# 2-22.net
KiCad netlist of a schematic drawn in Altium Designer
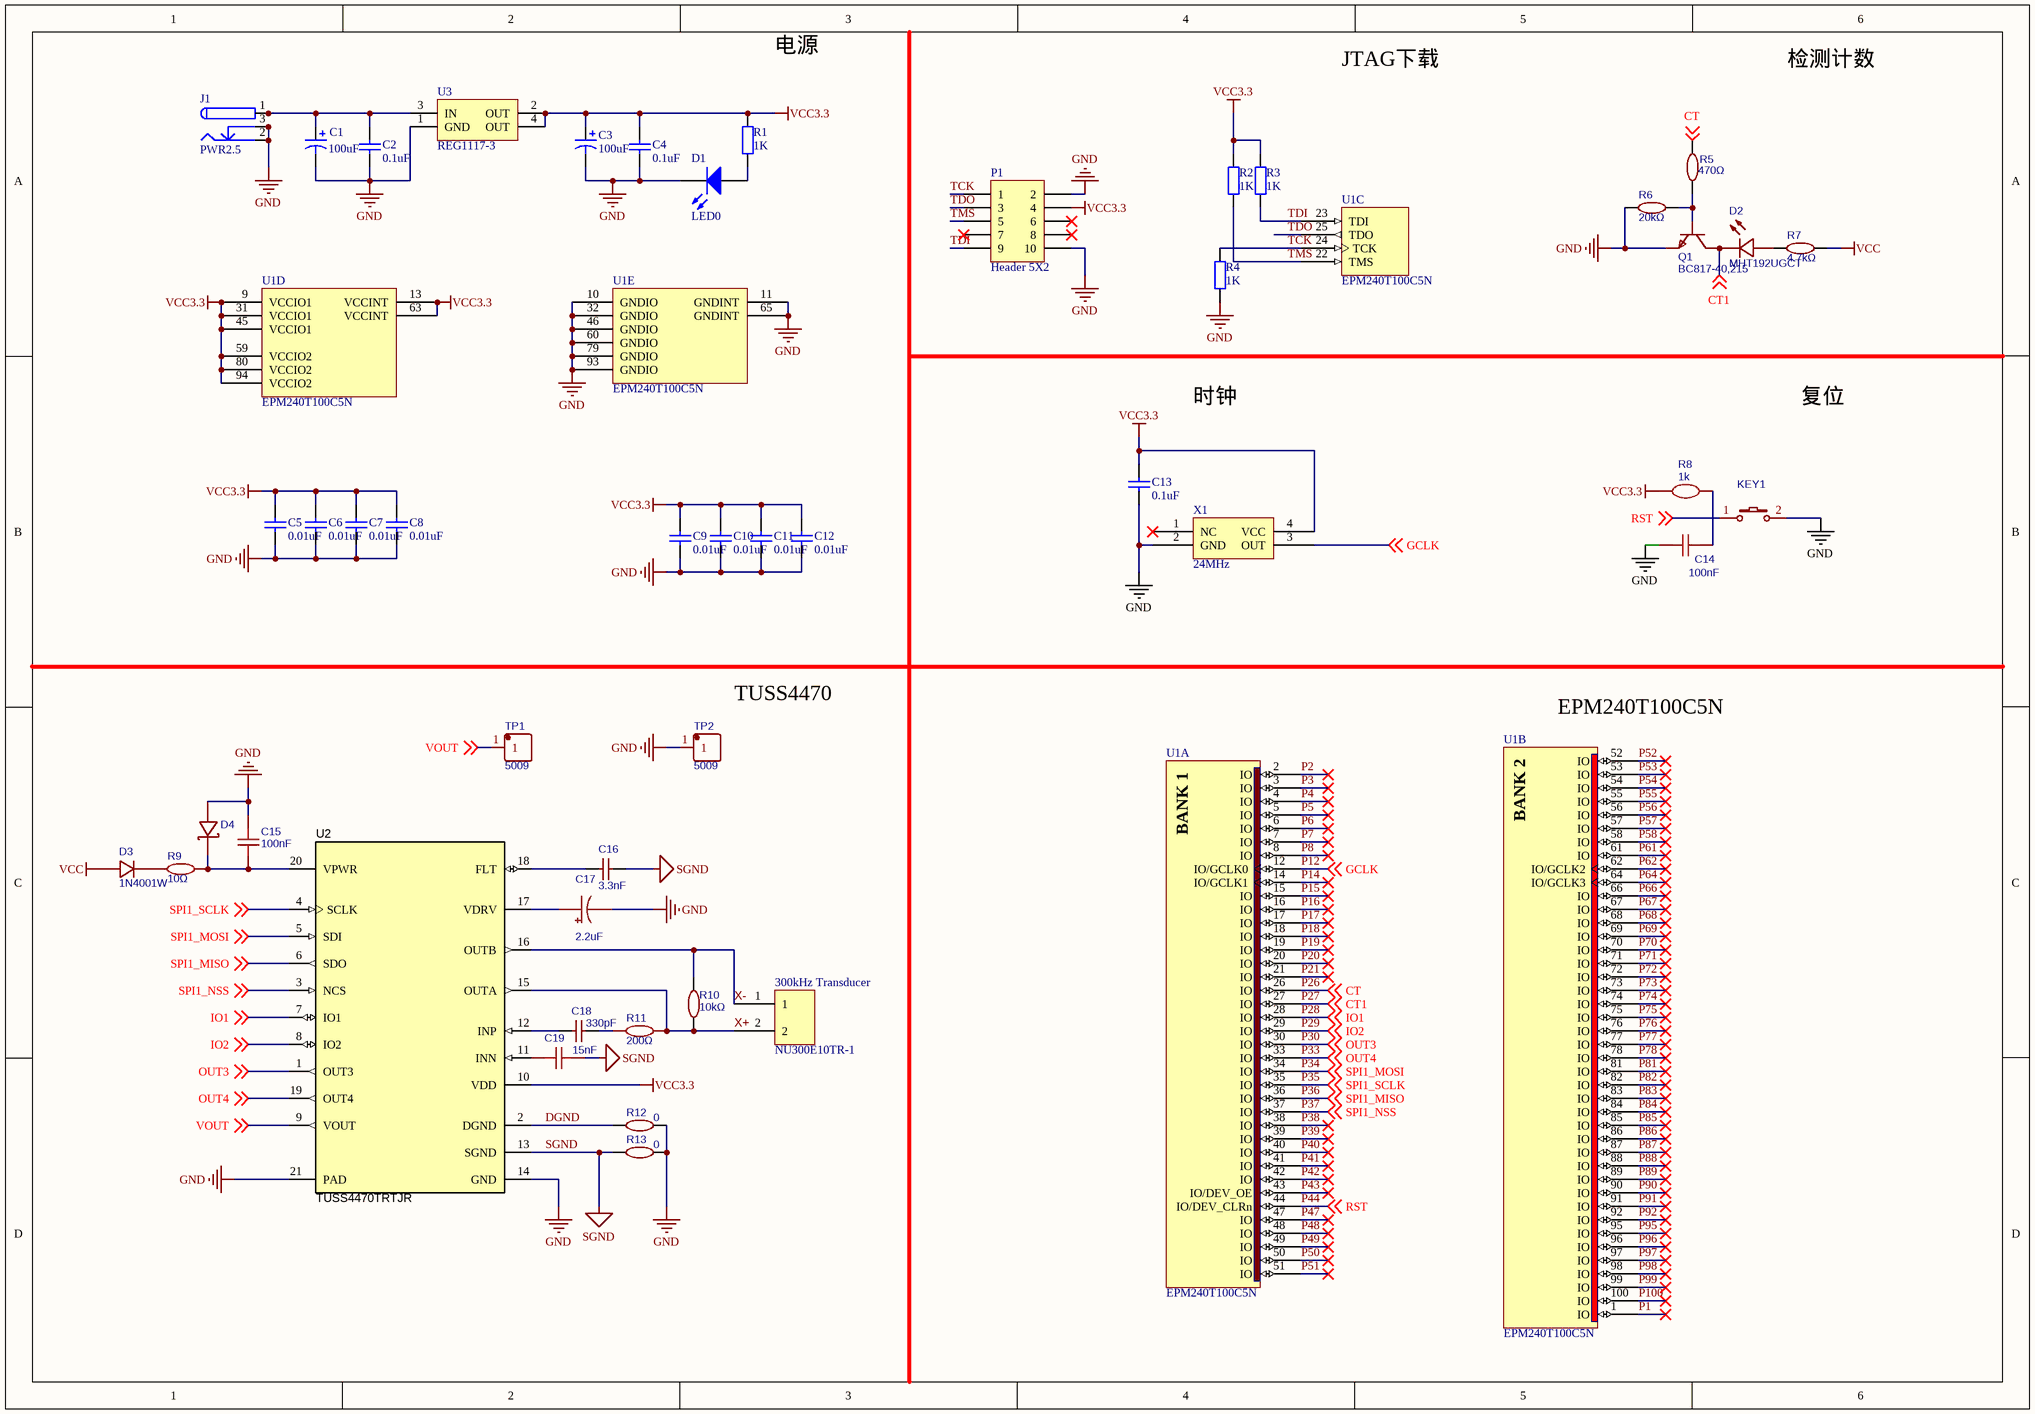
[diagram p0: 超声波接近电路2-22.SchDoc]

(export (version "E")
  (design (tool "Eeschema 10.0.6"))
  (components
    (comp (ref "300kHz Transducer")
      (value "NU300E10TR-1")
      (footprint "NU300E10TR-1")
      (libsource (lib "超声波接近电路") (part "NU300E10TR-1"))
    )
    (comp (ref "C1")
      (value "100uF")
      (footprint "CAP-SMD_L3.2-W1.6-RD")
      (description "Polarized Capacitor (Radial)")
      (fields (field (name "Comment") "Cap Pol1") (field (name "PUBLISHER") "Altium Limited"))
      (libsource (lib "Miscellaneous Devices") (part "Cap Pol1"))
    )
    (comp (ref "C2")
      (value "0.1uF")
      (footprint "C0603")
      (description "Capacitor")
      (fields (field (name "Comment") "Cap") (field (name "PUBLISHER") "Altium Limited"))
      (libsource (lib "Miscellaneous Devices") (part "Cap"))
    )
    (comp (ref "C3")
      (value "100uF")
      (footprint "CAP-SMD_L3.2-W1.6-RD")
      (description "Polarized Capacitor (Radial)")
      (fields (field (name "Comment") "Cap Pol1") (field (name "PUBLISHER") "Altium Limited"))
      (libsource (lib "Miscellaneous Devices") (part "Cap Pol1"))
    )
    (comp (ref "C4")
      (value "0.1uF")
      (footprint "C0603")
      (description "Capacitor")
      (fields (field (name "Comment") "Cap") (field (name "PUBLISHER") "Altium Limited"))
      (libsource (lib "Miscellaneous Devices") (part "Cap"))
    )
    (comp (ref "C5")
      (value "0.01uF")
      (footprint "C0603")
      (description "Capacitor")
      (fields (field (name "Comment") "Cap") (field (name "PUBLISHER") "Altium Limited"))
      (libsource (lib "Miscellaneous Devices") (part "Cap"))
    )
    (comp (ref "C6")
      (value "0.01uF")
      (footprint "C0603")
      (description "Capacitor")
      (fields (field (name "Comment") "Cap") (field (name "PUBLISHER") "Altium Limited"))
      (libsource (lib "Miscellaneous Devices") (part "Cap"))
    )
    (comp (ref "C7")
      (value "0.01uF")
      (footprint "C0603")
      (description "Capacitor")
      (fields (field (name "Comment") "Cap") (field (name "PUBLISHER") "Altium Limited"))
      (libsource (lib "Miscellaneous Devices") (part "Cap"))
    )
    (comp (ref "C8")
      (value "0.01uF")
      (footprint "C0603")
      (description "Capacitor")
      (fields (field (name "Comment") "Cap") (field (name "PUBLISHER") "Altium Limited"))
      (libsource (lib "Miscellaneous Devices") (part "Cap"))
    )
    (comp (ref "C9")
      (value "0.01uF")
      (footprint "C0603")
      (description "Capacitor")
      (fields (field (name "Comment") "Cap") (field (name "PUBLISHER") "Altium Limited"))
      (libsource (lib "Miscellaneous Devices") (part "Cap"))
    )
    (comp (ref "C10")
      (value "0.01uF")
      (footprint "C0603")
      (description "Capacitor")
      (fields (field (name "Comment") "Cap") (field (name "PUBLISHER") "Altium Limited"))
      (libsource (lib "Miscellaneous Devices") (part "Cap"))
    )
    (comp (ref "C11")
      (value "0.01uF")
      (footprint "C0603")
      (description "Capacitor")
      (fields (field (name "Comment") "Cap") (field (name "PUBLISHER") "Altium Limited"))
      (libsource (lib "Miscellaneous Devices") (part "Cap"))
    )
    (comp (ref "C12")
      (value "0.01uF")
      (footprint "C0603")
      (description "Capacitor")
      (fields (field (name "Comment") "Cap") (field (name "PUBLISHER") "Altium Limited"))
      (libsource (lib "Miscellaneous Devices") (part "Cap"))
    )
    (comp (ref "C13")
      (value "0.1uF")
      (footprint "C0603")
      (description "Capacitor")
      (fields (field (name "Comment") "Cap") (field (name "PUBLISHER") "Altium Limited"))
      (libsource (lib "Miscellaneous Devices") (part "Cap"))
    )
    (comp (ref "C14")
      (value "100nF")
      (footprint "C0603")
      (fields (field (name "CONTRIBUTOR") "LCEDA_Lib"))
      (libsource (lib "altium-import") (part "root_2_100nF_"))
    )
    (comp (ref "C15")
      (value "100nF")
      (footprint "C0603")
      (fields
        (field (name "BOM_MANUFACTURER PART") "CC0603KRX7R9BB104")
        (field (name "BOM_SUPPLIER PART") "C14663")
      )
      (libsource (lib "超声波接近电路") (part "100nF"))
    )
    (comp (ref "C16")
      (value "3.3nF")
      (footprint "C0603")
      (fields
        (field (name "BOM_MANUFACTURER PART") "GRM1885C1H332JA01D")
        (field (name "BOM_SUPPLIER PART") "C77036")
      )
      (libsource (lib "超声波接近电路") (part "3.3nF"))
    )
    (comp (ref "C17")
      (value "2.2uF")
      (footprint "CAP-SMD_L3.2-W1.6-RD")
      (fields
        (field (name "BOM_SUPPLIER PART") "C122264")
        (field (name "BOM_MANUFACTURER PART") "T491A225K035AT")
        (field (name "CONTRIBUTOR") "LCSC")
      )
      (libsource (lib "超声波接近电路") (part "2.2uF_1"))
    )
    (comp (ref "C18")
      (value "330pF")
      (footprint "C0603")
      (fields
        (field (name "BOM_MANUFACTURER PART") "CL10C331JB8NNNC")
        (field (name "BOM_SUPPLIER PART") "C1664")
      )
      (libsource (lib "超声波接近电路") (part "330pF"))
    )
    (comp (ref "C19")
      (value "15nF")
      (footprint "C0603")
      (fields
        (field (name "BOM_SUPPLIER PART") "C519550")
        (field (name "BOM_MANUFACTURER PART") "CC0603JRX7R9BB153")
        (field (name "CONTRIBUTOR") "LCSC")
      )
      (libsource (lib "超声波接近电路") (part "15nF"))
    )
    (comp (ref "D1")
      (value "LED0")
      (footprint "LED0603-RD_RED")
      (description "Typical INFRARED GaAs LED")
      (fields (field (name "PUBLISHER") "Altium Limited"))
      (libsource (lib "Miscellaneous Devices") (part "LED0"))
    )
    (comp (ref "D2")
      (value "MHT192UGCT")
      (footprint "LED0603-RD_GREEN")
      (fields (field (name "BOM_SUPPLIER PART") "C389519") (field (name "CONTRIBUTOR") "LCSC"))
      (libsource (lib "超声波接近电路") (part "MHT192UGCT"))
    )
    (comp (ref "D3")
      (value "1N4001W")
      (footprint "SOD-123F_L2.8-W1.8-LS3.7-RD")
      (fields (field (name "BOM_SUPPLIER PART") "C162732") (field (name "CONTRIBUTOR") "LCSC"))
      (libsource (lib "超声波接近电路") (part "1N4001W"))
    )
    (comp (ref "D4")
      (value "SMF36A_C353286")
      (footprint "SOD-123FL_L2.7-W1.8-LS3.8-RD")
      (fields
        (field (name "BOM_SUPPLIER PART") "C353286")
        (field (name "BOM_MANUFACTURER PART") "SMF36A")
        (field (name "CONTRIBUTOR") "LCSC")
      )
      (libsource (lib "超声波接近电路") (part "SMF36A_C353286"))
    )
    (comp (ref "J1")
      (value "PWR2.5")
      (footprint "KLD-0202")
      (description "Low Voltage Power Supply Connector")
      (fields (field (name "PUBLISHER") "Altium Limited"))
      (libsource (lib "Miscellaneous Connectors") (part "PWR2.5"))
    )
    (comp (ref "KEY1")
      (value "K2-3.6×6.1_SMD")
      (footprint "KEY-SMD_2P-L6.2-W3.6-LS8.0")
      (fields
        (field (name "BOM_SUPPLIER PART") "C118141")
        (field (name "BOM_MANUFACTURER PART") "K2-1107ST-A4SW-06")
        (field (name "CONTRIBUTOR") "LCEDA_Lib")
      )
      (libsource (lib "altium-import") (part "root_0_K2-3.6×6.1_SMD_"))
    )
    (comp (ref "P1")
      (value "Header 5X2")
      (footprint "HDR2X5")
      (description "Header, 5-Pin, Dual row")
      (fields (field (name "PUBLISHER") "Altium Limited"))
      (libsource (lib "Miscellaneous Connectors") (part "Header 5X2"))
    )
    (comp (ref "Q1")
      (value "BC817-40,215")
      (footprint "SOT-23-3_L2.9-W1.6-P1.90-LS2.8-BR")
      (fields (field (name "BOM_SUPPLIER PART") "C52801"))
      (libsource (lib "超声波接近电路") (part "BC817-40,215"))
    )
    (comp (ref "R1")
      (value "1K")
      (footprint "R0603")
      (description "Resistor")
      (fields (field (name "Comment") "Res2") (field (name "PUBLISHER") "Altium Limited"))
      (libsource (lib "Miscellaneous Devices") (part "Res2"))
    )
    (comp (ref "R2")
      (value "1K")
      (footprint "R0603")
      (description "Resistor")
      (fields (field (name "Comment") "Res2") (field (name "PUBLISHER") "Altium Limited"))
      (libsource (lib "Miscellaneous Devices") (part "Res2"))
    )
    (comp (ref "R3")
      (value "1K")
      (footprint "R0603")
      (description "Resistor")
      (fields (field (name "Comment") "Res2") (field (name "PUBLISHER") "Altium Limited"))
      (libsource (lib "Miscellaneous Devices") (part "Res2"))
    )
    (comp (ref "R4")
      (value "1K")
      (footprint "R0603")
      (description "Resistor")
      (fields (field (name "Comment") "Res2") (field (name "PUBLISHER") "Altium Limited"))
      (libsource (lib "Miscellaneous Devices") (part "Res2"))
    )
    (comp (ref "R5")
      (value "470Ω")
      (footprint "R0603")
      (fields
        (field (name "BOM_MANUFACTURER PART") "0603WAJ0471T5E")
        (field (name "BOM_SUPPLIER PART") "C25241")
      )
      (libsource (lib "超声波接近电路") (part "470Ω"))
    )
    (comp (ref "R6")
      (value "20kΩ")
      (footprint "R0603")
      (fields
        (field (name "BOM_MANUFACTURER PART") "0603WAF2002T5E")
        (field (name "BOM_SUPPLIER PART") "C4184")
      )
      (libsource (lib "超声波接近电路") (part "20kΩ"))
    )
    (comp (ref "R7")
      (value "4.7kΩ")
      (footprint "R0603")
      (fields
        (field (name "BOM_MANUFACTURER PART") "0603WAF4701T5E")
        (field (name "BOM_SUPPLIER PART") "C23162")
      )
      (libsource (lib "超声波接近电路") (part "4.7kΩ"))
    )
    (comp (ref "R8")
      (value "1k")
      (footprint "R0603")
      (fields (field (name "CONTRIBUTOR") "LCEDA_Lib"))
      (libsource (lib "altium-import") (part "root_2_1k_"))
    )
    (comp (ref "R9")
      (value "10Ω")
      (footprint "R0603")
      (fields
        (field (name "BOM_SUPPLIER PART") "C441879")
        (field (name "BOM_MANUFACTURER PART") "ERJPA3J100V")
        (field (name "CONTRIBUTOR") "LCSC")
      )
      (libsource (lib "超声波接近电路") (part "10Ω"))
    )
    (comp (ref "R10")
      (value "10kΩ")
      (footprint "R0603")
      (fields
        (field (name "BOM_MANUFACTURER PART") "0603WAF1002T5E")
        (field (name "BOM_SUPPLIER PART") "C25804")
      )
      (libsource (lib "超声波接近电路") (part "10kΩ"))
    )
    (comp (ref "R11")
      (value "200Ω")
      (footprint "R0603")
      (fields
        (field (name "BOM_SUPPLIER PART") "C254528")
        (field (name "BOM_MANUFACTURER PART") "ERJ-PA3F2000V")
        (field (name "CONTRIBUTOR") "LCSC")
      )
      (libsource (lib "超声波接近电路") (part "200Ω"))
    )
    (comp (ref "R12")
      (value "0")
      (footprint "R0603")
      (fields
        (field (name "BOM_MANUFACTURER PART") "RC0603JR-070RL")
        (field (name "BOM_SUPPLIER PART") "C95177")
      )
      (libsource (lib "超声波接近电路") (part "0_1"))
    )
    (comp (ref "R13")
      (value "0")
      (footprint "R0603")
      (fields
        (field (name "BOM_MANUFACTURER PART") "RC0603JR-070RL")
        (field (name "BOM_SUPPLIER PART") "C95177")
      )
      (libsource (lib "超声波接近电路") (part "0_1"))
    )
    (comp (ref "TP1")
      (value "5009")
      (footprint "TEST-TH_BD3.18-P1.93")
      (fields (field (name "BOM_SUPPLIER PART") "C238126") (field (name "CONTRIBUTOR") "LCSC"))
      (libsource (lib "超声波接近电路") (part "5009"))
    )
    (comp (ref "TP2")
      (value "5009")
      (footprint "TEST-TH_BD3.18-P1.93")
      (fields (field (name "BOM_SUPPLIER PART") "C238126") (field (name "CONTRIBUTOR") "LCSC"))
      (libsource (lib "超声波接近电路") (part "5009"))
    )
    (comp (ref "U1")
      (value "EPM240T100C5N")
      (footprint "TQFP-100_L14.0-W14.0-P0.50-LS16.0-BL")
      (fields (field (name "PUBLISHER") "Altium Limited"))
      (libsource (lib "CPLD实验板") (part "EPM240T100C5N"))
    )
    (comp (ref "U2")
      (value "TUSS4470TRTJR")
      (footprint "QFN-20_L4.0-W4.0-P0.50-TL-EP2.7")
      (description "Ultrasonic Sensor Signal Conditioner IC for Directly")
      (fields
        (field (name "MANUFACTURER") "Texas Instruments")
        (field (name "ALTERNATE PARTNUMBER") "PGA44801RTJT")
        (field (name "PARTNUMBER") "TUSS4470TRTJR")
      )
      (libsource (lib "超声波接近电路") (part "CMP-0081414-4"))
    )
    (comp (ref "U3")
      (value "REG1117-3")
      (footprint "ZZ311")
      (description "800mA Low Dropout Positive Regulator Fixed 2.85V,3V,3.3V and 5V")
      (fields (field (name "PUBLISHER") "Altium Limited"))
      (libsource (lib "BB Power Mgt Voltage Regulator") (part "REG1117-3"))
    )
    (comp (ref "X1")
      (value "24MHz")
      (footprint "OSC-SMD_4P-L7.0-W5.0-BL_SIT1602")
      (libsource (lib "Schlib1") (part "oscillator"))
    )
  )
  (nets
    (net (code "1") (name "/DGND") (class "Default")
      (node (ref "R12") (pin "1") (pinfunction "1_1") (pintype "passive"))
      (node (ref "U2") (pin "2") (pinfunction "DGND_2") (pintype "power_in"))
    )
    (net (code "2") (name "/P1") (class "Default")
      (node (ref "U1") (pin "1") (pinfunction "IO_1") (pintype "bidirectional+no_connect"))
    )
    (net (code "3") (name "/P2") (class "Default")
      (node (ref "U1") (pin "2") (pinfunction "IO_2") (pintype "bidirectional+no_connect"))
    )
    (net (code "4") (name "/P3") (class "Default")
      (node (ref "U1") (pin "3") (pinfunction "IO_3") (pintype "bidirectional+no_connect"))
    )
    (net (code "5") (name "/P4") (class "Default")
      (node (ref "U1") (pin "4") (pinfunction "IO_4") (pintype "bidirectional+no_connect"))
    )
    (net (code "6") (name "/P5") (class "Default")
      (node (ref "U1") (pin "5") (pinfunction "IO_5") (pintype "bidirectional+no_connect"))
    )
    (net (code "7") (name "/P6") (class "Default")
      (node (ref "U1") (pin "6") (pinfunction "IO_6") (pintype "bidirectional+no_connect"))
    )
    (net (code "8") (name "/P7") (class "Default")
      (node (ref "U1") (pin "7") (pinfunction "IO_7") (pintype "bidirectional+no_connect"))
    )
    (net (code "9") (name "/P8") (class "Default")
      (node (ref "U1") (pin "8") (pinfunction "IO_8") (pintype "bidirectional+no_connect"))
    )
    (net (code "10") (name "/P14") (class "Default")
      (node (ref "U1") (pin "14") (pinfunction "IO/GCLK1_14") (pintype "bidirectional+no_connect"))
    )
    (net (code "11") (name "/P15") (class "Default")
      (node (ref "U1") (pin "15") (pinfunction "IO_15") (pintype "bidirectional+no_connect"))
    )
    (net (code "12") (name "/P16") (class "Default")
      (node (ref "U1") (pin "16") (pinfunction "IO_16") (pintype "bidirectional+no_connect"))
    )
    (net (code "13") (name "/P17") (class "Default")
      (node (ref "U1") (pin "17") (pinfunction "IO_17") (pintype "bidirectional+no_connect"))
    )
    (net (code "14") (name "/P18") (class "Default")
      (node (ref "U1") (pin "18") (pinfunction "IO_18") (pintype "bidirectional+no_connect"))
    )
    (net (code "15") (name "/P19") (class "Default")
      (node (ref "U1") (pin "19") (pinfunction "IO_19") (pintype "bidirectional+no_connect"))
    )
    (net (code "16") (name "/P20") (class "Default")
      (node (ref "U1") (pin "20") (pinfunction "IO_20") (pintype "bidirectional+no_connect"))
    )
    (net (code "17") (name "/P21") (class "Default")
      (node (ref "U1") (pin "21") (pinfunction "IO_21") (pintype "bidirectional+no_connect"))
    )
    (net (code "18") (name "/P38") (class "Default")
      (node (ref "U1") (pin "38") (pinfunction "IO_38") (pintype "bidirectional+no_connect"))
    )
    (net (code "19") (name "/P39") (class "Default")
      (node (ref "U1") (pin "39") (pinfunction "IO_39") (pintype "bidirectional+no_connect"))
    )
    (net (code "20") (name "/P40") (class "Default")
      (node (ref "U1") (pin "40") (pinfunction "IO_40") (pintype "bidirectional+no_connect"))
    )
    (net (code "21") (name "/P41") (class "Default")
      (node (ref "U1") (pin "41") (pinfunction "IO_41") (pintype "bidirectional+no_connect"))
    )
    (net (code "22") (name "/P42") (class "Default")
      (node (ref "U1") (pin "42") (pinfunction "IO_42") (pintype "bidirectional+no_connect"))
    )
    (net (code "23") (name "/P43") (class "Default")
      (node (ref "U1") (pin "43") (pinfunction "IO/DEV_OE_43") (pintype "bidirectional+no_connect"))
    )
    (net (code "24") (name "/P47") (class "Default")
      (node (ref "U1") (pin "47") (pinfunction "IO_47") (pintype "bidirectional+no_connect"))
    )
    (net (code "25") (name "/P48") (class "Default")
      (node (ref "U1") (pin "48") (pinfunction "IO_48") (pintype "bidirectional+no_connect"))
    )
    (net (code "26") (name "/P49") (class "Default")
      (node (ref "U1") (pin "49") (pinfunction "IO_49") (pintype "bidirectional+no_connect"))
    )
    (net (code "27") (name "/P50") (class "Default")
      (node (ref "U1") (pin "50") (pinfunction "IO_50") (pintype "bidirectional+no_connect"))
    )
    (net (code "28") (name "/P51") (class "Default")
      (node (ref "U1") (pin "51") (pinfunction "IO_51") (pintype "bidirectional+no_connect"))
    )
    (net (code "29") (name "/P52") (class "Default")
      (node (ref "U1") (pin "52") (pinfunction "IO_52") (pintype "bidirectional+no_connect"))
    )
    (net (code "30") (name "/P53") (class "Default")
      (node (ref "U1") (pin "53") (pinfunction "IO_53") (pintype "bidirectional+no_connect"))
    )
    (net (code "31") (name "/P54") (class "Default")
      (node (ref "U1") (pin "54") (pinfunction "IO_54") (pintype "bidirectional+no_connect"))
    )
    (net (code "32") (name "/P55") (class "Default")
      (node (ref "U1") (pin "55") (pinfunction "IO_55") (pintype "bidirectional+no_connect"))
    )
    (net (code "33") (name "/P56") (class "Default")
      (node (ref "U1") (pin "56") (pinfunction "IO_56") (pintype "bidirectional+no_connect"))
    )
    (net (code "34") (name "/P57") (class "Default")
      (node (ref "U1") (pin "57") (pinfunction "IO_57") (pintype "bidirectional+no_connect"))
    )
    (net (code "35") (name "/P58") (class "Default")
      (node (ref "U1") (pin "58") (pinfunction "IO_58") (pintype "bidirectional+no_connect"))
    )
    (net (code "36") (name "/P61") (class "Default")
      (node (ref "U1") (pin "61") (pinfunction "IO_61") (pintype "bidirectional+no_connect"))
    )
    (net (code "37") (name "/P62") (class "Default")
      (node (ref "U1") (pin "62") (pinfunction "IO/GCLK2_62") (pintype "bidirectional+no_connect"))
    )
    (net (code "38") (name "/P64") (class "Default")
      (node (ref "U1") (pin "64") (pinfunction "IO/GCLK3_64") (pintype "bidirectional+no_connect"))
    )
    (net (code "39") (name "/P66") (class "Default")
      (node (ref "U1") (pin "66") (pinfunction "IO_66") (pintype "bidirectional+no_connect"))
    )
    (net (code "40") (name "/P67") (class "Default")
      (node (ref "U1") (pin "67") (pinfunction "IO_67") (pintype "bidirectional+no_connect"))
    )
    (net (code "41") (name "/P68") (class "Default")
      (node (ref "U1") (pin "68") (pinfunction "IO_68") (pintype "bidirectional+no_connect"))
    )
    (net (code "42") (name "/P69") (class "Default")
      (node (ref "U1") (pin "69") (pinfunction "IO_69") (pintype "bidirectional+no_connect"))
    )
    (net (code "43") (name "/P70") (class "Default")
      (node (ref "U1") (pin "70") (pinfunction "IO_70") (pintype "bidirectional+no_connect"))
    )
    (net (code "44") (name "/P71") (class "Default")
      (node (ref "U1") (pin "71") (pinfunction "IO_71") (pintype "bidirectional+no_connect"))
    )
    (net (code "45") (name "/P72") (class "Default")
      (node (ref "U1") (pin "72") (pinfunction "IO_72") (pintype "bidirectional+no_connect"))
    )
    (net (code "46") (name "/P73") (class "Default")
      (node (ref "U1") (pin "73") (pinfunction "IO_73") (pintype "bidirectional+no_connect"))
    )
    (net (code "47") (name "/P74") (class "Default")
      (node (ref "U1") (pin "74") (pinfunction "IO_74") (pintype "bidirectional+no_connect"))
    )
    (net (code "48") (name "/P75") (class "Default")
      (node (ref "U1") (pin "75") (pinfunction "IO_75") (pintype "bidirectional+no_connect"))
    )
    (net (code "49") (name "/P76") (class "Default")
      (node (ref "U1") (pin "76") (pinfunction "IO_76") (pintype "bidirectional+no_connect"))
    )
    (net (code "50") (name "/P77") (class "Default")
      (node (ref "U1") (pin "77") (pinfunction "IO_77") (pintype "bidirectional+no_connect"))
    )
    (net (code "51") (name "/P78") (class "Default")
      (node (ref "U1") (pin "78") (pinfunction "IO_78") (pintype "bidirectional+no_connect"))
    )
    (net (code "52") (name "/P81") (class "Default")
      (node (ref "U1") (pin "81") (pinfunction "IO_81") (pintype "bidirectional+no_connect"))
    )
    (net (code "53") (name "/P82") (class "Default")
      (node (ref "U1") (pin "82") (pinfunction "IO_82") (pintype "bidirectional+no_connect"))
    )
    (net (code "54") (name "/P83") (class "Default")
      (node (ref "U1") (pin "83") (pinfunction "IO_83") (pintype "bidirectional+no_connect"))
    )
    (net (code "55") (name "/P84") (class "Default")
      (node (ref "U1") (pin "84") (pinfunction "IO_84") (pintype "bidirectional+no_connect"))
    )
    (net (code "56") (name "/P85") (class "Default")
      (node (ref "U1") (pin "85") (pinfunction "IO_85") (pintype "bidirectional+no_connect"))
    )
    (net (code "57") (name "/P86") (class "Default")
      (node (ref "U1") (pin "86") (pinfunction "IO_86") (pintype "bidirectional+no_connect"))
    )
    (net (code "58") (name "/P87") (class "Default")
      (node (ref "U1") (pin "87") (pinfunction "IO_87") (pintype "bidirectional+no_connect"))
    )
    (net (code "59") (name "/P88") (class "Default")
      (node (ref "U1") (pin "88") (pinfunction "IO_88") (pintype "bidirectional+no_connect"))
    )
    (net (code "60") (name "/P89") (class "Default")
      (node (ref "U1") (pin "89") (pinfunction "IO_89") (pintype "bidirectional+no_connect"))
    )
    (net (code "61") (name "/P90") (class "Default")
      (node (ref "U1") (pin "90") (pinfunction "IO_90") (pintype "bidirectional+no_connect"))
    )
    (net (code "62") (name "/P91") (class "Default")
      (node (ref "U1") (pin "91") (pinfunction "IO_91") (pintype "bidirectional+no_connect"))
    )
    (net (code "63") (name "/P92") (class "Default")
      (node (ref "U1") (pin "92") (pinfunction "IO_92") (pintype "bidirectional+no_connect"))
    )
    (net (code "64") (name "/P95") (class "Default")
      (node (ref "U1") (pin "95") (pinfunction "IO_95") (pintype "bidirectional+no_connect"))
    )
    (net (code "65") (name "/P96") (class "Default")
      (node (ref "U1") (pin "96") (pinfunction "IO_96") (pintype "bidirectional+no_connect"))
    )
    (net (code "66") (name "/P97") (class "Default")
      (node (ref "U1") (pin "97") (pinfunction "IO_97") (pintype "bidirectional+no_connect"))
    )
    (net (code "67") (name "/P98") (class "Default")
      (node (ref "U1") (pin "98") (pinfunction "IO_98") (pintype "bidirectional+no_connect"))
    )
    (net (code "68") (name "/P99") (class "Default")
      (node (ref "U1") (pin "99") (pinfunction "IO_99") (pintype "bidirectional+no_connect"))
    )
    (net (code "69") (name "/P100") (class "Default")
      (node (ref "U1") (pin "100") (pinfunction "IO_100") (pintype "bidirectional+no_connect"))
    )
    (net (code "70") (name "/TCK") (class "Default")
      (node (ref "P1") (pin "1") (pinfunction "1_1") (pintype "passive"))
      (node (ref "R4") (pin "2") (pinfunction "2_2") (pintype "passive"))
      (node (ref "U1") (pin "24") (pinfunction "TCK_24") (pintype "input"))
    )
    (net (code "71") (name "/TDI") (class "Default")
      (node (ref "P1") (pin "9") (pinfunction "9_9") (pintype "passive"))
      (node (ref "R3") (pin "1") (pinfunction "1_1") (pintype "passive"))
      (node (ref "U1") (pin "23") (pinfunction "TDI_23") (pintype "input"))
    )
    (net (code "72") (name "/TDO") (class "Default")
      (node (ref "P1") (pin "3") (pinfunction "3_3") (pintype "passive"))
      (node (ref "U1") (pin "25") (pinfunction "TDO_25") (pintype "output"))
    )
    (net (code "73") (name "/TMS") (class "Default")
      (node (ref "P1") (pin "5") (pinfunction "5_5") (pintype "passive"))
      (node (ref "R2") (pin "1") (pinfunction "1_1") (pintype "passive"))
      (node (ref "U1") (pin "22") (pinfunction "TMS_22") (pintype "input"))
    )
    (net (code "74") (name "/X+") (class "Default")
      (node (ref "300kHz Transducer") (pin "2") (pinfunction "2_2") (pintype "passive"))
      (node (ref "R10") (pin "1") (pinfunction "1_1") (pintype "passive"))
      (node (ref "R11") (pin "2") (pinfunction "2_2") (pintype "passive"))
      (node (ref "U2") (pin "15") (pinfunction "OUTA_15") (pintype "output"))
    )
    (net (code "75") (name "/X-") (class "Default")
      (node (ref "300kHz Transducer") (pin "1") (pinfunction "1_1") (pintype "passive"))
      (node (ref "R10") (pin "2") (pinfunction "2_2") (pintype "passive"))
      (node (ref "U2") (pin "16") (pinfunction "OUTB_16") (pintype "output"))
    )
    (net (code "76") (name "CT") (class "Default")
      (node (ref "R5") (pin "1") (pinfunction "1_1") (pintype "passive"))
      (node (ref "U1") (pin "26") (pinfunction "IO_26") (pintype "bidirectional"))
    )
    (net (code "77") (name "CT1") (class "Default")
      (node (ref "D2") (pin "1") (pinfunction "-_1") (pintype "passive"))
      (node (ref "Q1") (pin "3") (pinfunction "3_3") (pintype "passive"))
      (node (ref "U1") (pin "27") (pinfunction "IO_27") (pintype "bidirectional"))
    )
    (net (code "78") (name "GCLK") (class "Default")
      (node (ref "U1") (pin "12") (pinfunction "IO/GCLK0_12") (pintype "bidirectional"))
      (node (ref "X1") (pin "3") (pinfunction "OUT_3") (pintype "passive"))
    )
    (net (code "79") (name "GND") (class "Default")
      (node (ref "C1") (pin "2") (pinfunction "2_2") (pintype "passive"))
      (node (ref "C10") (pin "1") (pinfunction "1_1") (pintype "passive"))
      (node (ref "C11") (pin "1") (pinfunction "1_1") (pintype "passive"))
      (node (ref "C12") (pin "1") (pinfunction "1_1") (pintype "passive"))
      (node (ref "C13") (pin "1") (pinfunction "1_1") (pintype "passive"))
      (node (ref "C14") (pin "2") (pinfunction "2_2") (pintype "passive"))
      (node (ref "C15") (pin "2") (pinfunction "2_2") (pintype "passive"))
      (node (ref "C17") (pin "2") (pinfunction "2_2") (pintype "passive"))
      (node (ref "C2") (pin "2") (pinfunction "2_2") (pintype "passive"))
      (node (ref "C3") (pin "2") (pinfunction "2_2") (pintype "passive"))
      (node (ref "C4") (pin "2") (pinfunction "2_2") (pintype "passive"))
      (node (ref "C5") (pin "1") (pinfunction "1_1") (pintype "passive"))
      (node (ref "C6") (pin "1") (pinfunction "1_1") (pintype "passive"))
      (node (ref "C7") (pin "1") (pinfunction "1_1") (pintype "passive"))
      (node (ref "C8") (pin "1") (pinfunction "1_1") (pintype "passive"))
      (node (ref "C9") (pin "1") (pinfunction "1_1") (pintype "passive"))
      (node (ref "D1") (pin "2") (pinfunction "K_2") (pintype "passive"))
      (node (ref "D4") (pin "2") (pinfunction "A_2") (pintype "passive"))
      (node (ref "J1") (pin "2") (pinfunction "2_2") (pintype "power_in"))
      (node (ref "J1") (pin "2A") (pinfunction "2A_2A") (pintype "power_in"))
      (node (ref "J1") (pin "2B") (pinfunction "2B_2B") (pintype "power_in"))
      (node (ref "J1") (pin "3") (pinfunction "3_3") (pintype "power_in"))
      (node (ref "J1") (pin "3A") (pinfunction "3A_3A") (pintype "power_in"))
      (node (ref "J1") (pin "3B") (pinfunction "3B_3B") (pintype "power_in"))
      (node (ref "KEY1") (pin "2") (pinfunction "2_2") (pintype "passive"))
      (node (ref "P1") (pin "10") (pinfunction "10_10") (pintype "passive"))
      (node (ref "P1") (pin "2") (pinfunction "2_2") (pintype "passive"))
      (node (ref "Q1") (pin "2") (pinfunction "2_2") (pintype "passive"))
      (node (ref "R12") (pin "2") (pinfunction "2_2") (pintype "passive"))
      (node (ref "R13") (pin "2") (pinfunction "2_2") (pintype "passive"))
      (node (ref "R4") (pin "1") (pinfunction "1_1") (pintype "passive"))
      (node (ref "R6") (pin "1") (pinfunction "1_1") (pintype "passive"))
      (node (ref "TP2") (pin "1") (pinfunction "1_1") (pintype "passive"))
      (node (ref "U1") (pin "10") (pinfunction "GNDIO_10") (pintype "power_in"))
      (node (ref "U1") (pin "11") (pinfunction "GNDINT_11") (pintype "power_in"))
      (node (ref "U1") (pin "32") (pinfunction "GNDIO_32") (pintype "power_in"))
      (node (ref "U1") (pin "46") (pinfunction "GNDIO_46") (pintype "power_in"))
      (node (ref "U1") (pin "60") (pinfunction "GNDIO_60") (pintype "power_in"))
      (node (ref "U1") (pin "65") (pinfunction "GNDINT_65") (pintype "power_in"))
      (node (ref "U1") (pin "79") (pinfunction "GNDIO_79") (pintype "power_in"))
      (node (ref "U1") (pin "93") (pinfunction "GNDIO_93") (pintype "power_in"))
      (node (ref "U2") (pin "14") (pinfunction "GND_14") (pintype "power_in"))
      (node (ref "U2") (pin "21") (pinfunction "PAD_21") (pintype "passive"))
      (node (ref "U3") (pin "1") (pinfunction "GND_1") (pintype "power_in"))
      (node (ref "X1") (pin "2") (pinfunction "GND_2") (pintype "passive"))
    )
    (net (code "80") (name "IO1") (class "Default")
      (node (ref "U1") (pin "28") (pinfunction "IO_28") (pintype "bidirectional"))
      (node (ref "U2") (pin "7") (pinfunction "IO1_7") (pintype "bidirectional"))
    )
    (net (code "81") (name "IO2") (class "Default")
      (node (ref "U1") (pin "29") (pinfunction "IO_29") (pintype "bidirectional"))
      (node (ref "U2") (pin "8") (pinfunction "IO2_8") (pintype "bidirectional"))
    )
    (net (code "82") (name "Net-(C14-Pad1)") (class "Default")
      (node (ref "C14") (pin "1") (pinfunction "1_1") (pintype "passive"))
      (node (ref "R8") (pin "1") (pinfunction "1_1") (pintype "passive"))
    )
    (net (code "83") (name "Net-(C18-Pad2)") (class "Default")
      (node (ref "C18") (pin "2") (pinfunction "2_2") (pintype "passive"))
      (node (ref "R11") (pin "1") (pinfunction "1_1") (pintype "passive"))
    )
    (net (code "84") (name "Net-(D1-A)") (class "Default")
      (node (ref "D1") (pin "1") (pinfunction "A_1") (pintype "passive"))
      (node (ref "R1") (pin "1") (pinfunction "1_1") (pintype "passive"))
    )
    (net (code "85") (name "Net-(D2-+)") (class "Default")
      (node (ref "D2") (pin "2") (pinfunction "+_2") (pintype "passive"))
      (node (ref "R7") (pin "1") (pinfunction "1_1") (pintype "passive"))
    )
    (net (code "86") (name "Net-(D3-C)") (class "Default")
      (node (ref "D3") (pin "1") (pinfunction "C_1") (pintype "passive"))
      (node (ref "R9") (pin "1") (pinfunction "1_1") (pintype "passive"))
    )
    (net (code "87") (name "Net-(D4-K)") (class "Default")
      (node (ref "C15") (pin "1") (pinfunction "1_1") (pintype "passive"))
      (node (ref "D4") (pin "1") (pinfunction "K_1") (pintype "passive"))
      (node (ref "R9") (pin "2") (pinfunction "2_2") (pintype "passive"))
      (node (ref "U2") (pin "20") (pinfunction "VPWR_20") (pintype "power_in"))
    )
    (net (code "88") (name "Net-(Q1-Pad1)") (class "Default")
      (node (ref "Q1") (pin "1") (pinfunction "1_1") (pintype "passive"))
      (node (ref "R5") (pin "2") (pinfunction "2_2") (pintype "passive"))
      (node (ref "R6") (pin "2") (pinfunction "2_2") (pintype "passive"))
    )
    (net (code "89") (name "Net-(U2-FLT)") (class "Default")
      (node (ref "C16") (pin "1") (pinfunction "1_1") (pintype "passive"))
      (node (ref "U2") (pin "18") (pinfunction "FLT_18") (pintype "bidirectional"))
    )
    (net (code "90") (name "Net-(U2-INN)") (class "Default")
      (node (ref "C19") (pin "1") (pinfunction "1_1") (pintype "passive"))
      (node (ref "U2") (pin "11") (pinfunction "INN_11") (pintype "input"))
    )
    (net (code "91") (name "Net-(U2-INP)") (class "Default")
      (node (ref "C18") (pin "1") (pinfunction "1_1") (pintype "passive"))
      (node (ref "U2") (pin "12") (pinfunction "INP_12") (pintype "input"))
    )
    (net (code "92") (name "Net-(U2-VDRV)") (class "Default")
      (node (ref "C17") (pin "1") (pinfunction "1_1") (pintype "passive"))
      (node (ref "U2") (pin "17") (pinfunction "VDRV_17") (pintype "power_in"))
    )
    (net (code "93") (name "Net-(U3-IN)") (class "Default")
      (node (ref "C1") (pin "1") (pinfunction "1_1") (pintype "passive"))
      (node (ref "C2") (pin "1") (pinfunction "1_1") (pintype "passive"))
      (node (ref "J1") (pin "1") (pinfunction "1_1") (pintype "power_in"))
      (node (ref "J1") (pin "1A") (pinfunction "1A_1A") (pintype "power_in"))
      (node (ref "J1") (pin "1B") (pinfunction "1B_1B") (pintype "power_in"))
      (node (ref "U3") (pin "3") (pinfunction "IN_3") (pintype "power_in"))
    )
    (net (code "94") (name "OUT3") (class "Default")
      (node (ref "U1") (pin "30") (pinfunction "IO_30") (pintype "bidirectional"))
      (node (ref "U2") (pin "1") (pinfunction "OUT3_1") (pintype "output"))
    )
    (net (code "95") (name "OUT4") (class "Default")
      (node (ref "U1") (pin "33") (pinfunction "IO_33") (pintype "bidirectional"))
      (node (ref "U2") (pin "19") (pinfunction "OUT4_19") (pintype "output"))
    )
    (net (code "96") (name "RST") (class "Default")
      (node (ref "KEY1") (pin "1") (pinfunction "1_1") (pintype "passive"))
      (node (ref "U1") (pin "44") (pinfunction "IO/DEV_CLRn_44") (pintype "bidirectional"))
    )
    (net (code "97") (name "SGND") (class "Default")
      (node (ref "C16") (pin "2") (pinfunction "2_2") (pintype "passive"))
      (node (ref "C19") (pin "2") (pinfunction "2_2") (pintype "passive"))
      (node (ref "R13") (pin "1") (pinfunction "1_1") (pintype "passive"))
      (node (ref "U2") (pin "13") (pinfunction "SGND_13") (pintype "power_in"))
    )
    (net (code "98") (name "SPI1_MISO") (class "Default")
      (node (ref "U1") (pin "36") (pinfunction "IO_36") (pintype "bidirectional"))
      (node (ref "U2") (pin "6") (pinfunction "SDO_6") (pintype "output"))
    )
    (net (code "99") (name "SPI1_MOSI") (class "Default")
      (node (ref "U1") (pin "34") (pinfunction "IO_34") (pintype "bidirectional"))
      (node (ref "U2") (pin "5") (pinfunction "SDI_5") (pintype "input"))
    )
    (net (code "100") (name "SPI1_NSS") (class "Default")
      (node (ref "U1") (pin "37") (pinfunction "IO_37") (pintype "bidirectional"))
      (node (ref "U2") (pin "3") (pinfunction "NCS_3") (pintype "input"))
    )
    (net (code "101") (name "SPI1_SCLK") (class "Default")
      (node (ref "U1") (pin "35") (pinfunction "IO_35") (pintype "bidirectional"))
      (node (ref "U2") (pin "4") (pinfunction "SCLK_4") (pintype "input"))
    )
    (net (code "102") (name "VCC") (class "Default")
      (node (ref "D3") (pin "2") (pinfunction "A_2") (pintype "passive"))
      (node (ref "R7") (pin "2") (pinfunction "2_2") (pintype "passive"))
    )
    (net (code "103") (name "VCC3.3") (class "Default")
      (node (ref "C10") (pin "2") (pinfunction "2_2") (pintype "passive"))
      (node (ref "C11") (pin "2") (pinfunction "2_2") (pintype "passive"))
      (node (ref "C12") (pin "2") (pinfunction "2_2") (pintype "passive"))
      (node (ref "C13") (pin "2") (pinfunction "2_2") (pintype "passive"))
      (node (ref "C3") (pin "1") (pinfunction "1_1") (pintype "passive"))
      (node (ref "C4") (pin "1") (pinfunction "1_1") (pintype "passive"))
      (node (ref "C5") (pin "2") (pinfunction "2_2") (pintype "passive"))
      (node (ref "C6") (pin "2") (pinfunction "2_2") (pintype "passive"))
      (node (ref "C7") (pin "2") (pinfunction "2_2") (pintype "passive"))
      (node (ref "C8") (pin "2") (pinfunction "2_2") (pintype "passive"))
      (node (ref "C9") (pin "2") (pinfunction "2_2") (pintype "passive"))
      (node (ref "P1") (pin "4") (pinfunction "4_4") (pintype "passive"))
      (node (ref "R1") (pin "2") (pinfunction "2_2") (pintype "passive"))
      (node (ref "R2") (pin "2") (pinfunction "2_2") (pintype "passive"))
      (node (ref "R3") (pin "2") (pinfunction "2_2") (pintype "passive"))
      (node (ref "R8") (pin "2") (pinfunction "2_2") (pintype "passive"))
      (node (ref "U1") (pin "13") (pinfunction "VCCINT_13") (pintype "power_in"))
      (node (ref "U1") (pin "31") (pinfunction "VCCIO1_31") (pintype "power_in"))
      (node (ref "U1") (pin "45") (pinfunction "VCCIO1_45") (pintype "power_in"))
      (node (ref "U1") (pin "59") (pinfunction "VCCIO2_59") (pintype "power_in"))
      (node (ref "U1") (pin "63") (pinfunction "VCCINT_63") (pintype "power_in"))
      (node (ref "U1") (pin "80") (pinfunction "VCCIO2_80") (pintype "power_in"))
      (node (ref "U1") (pin "9") (pinfunction "VCCIO1_9") (pintype "power_in"))
      (node (ref "U1") (pin "94") (pinfunction "VCCIO2_94") (pintype "power_in"))
      (node (ref "U2") (pin "10") (pinfunction "VDD_10") (pintype "power_in"))
      (node (ref "U3") (pin "2") (pinfunction "OUT_2") (pintype "power_in"))
      (node (ref "U3") (pin "4") (pinfunction "OUT_4") (pintype "power_in"))
      (node (ref "X1") (pin "4") (pinfunction "VCC_4") (pintype "passive"))
    )
    (net (code "104") (name "VOUT") (class "Default")
      (node (ref "TP1") (pin "1") (pinfunction "1_1") (pintype "passive"))
      (node (ref "U2") (pin "9") (pinfunction "VOUT_9") (pintype "output"))
    )
    (net (code "105") (name "unconnected-(P1-Pad6)") (class "Default")
      (node (ref "P1") (pin "6") (pinfunction "6_6") (pintype "passive+no_connect"))
    )
    (net (code "106") (name "unconnected-(P1-Pad7)") (class "Default")
      (node (ref "P1") (pin "7") (pinfunction "7_7") (pintype "passive+no_connect"))
    )
    (net (code "107") (name "unconnected-(P1-Pad8)") (class "Default")
      (node (ref "P1") (pin "8") (pinfunction "8_8") (pintype "passive+no_connect"))
    )
    (net (code "108") (name "unconnected-(X1-NC-Pad1)") (class "Default")
      (node (ref "X1") (pin "1") (pinfunction "NC_1") (pintype "passive+no_connect"))
    )
  )
)
